# Button.net
KiCad netlist of a schematic drawn in Altium Designer
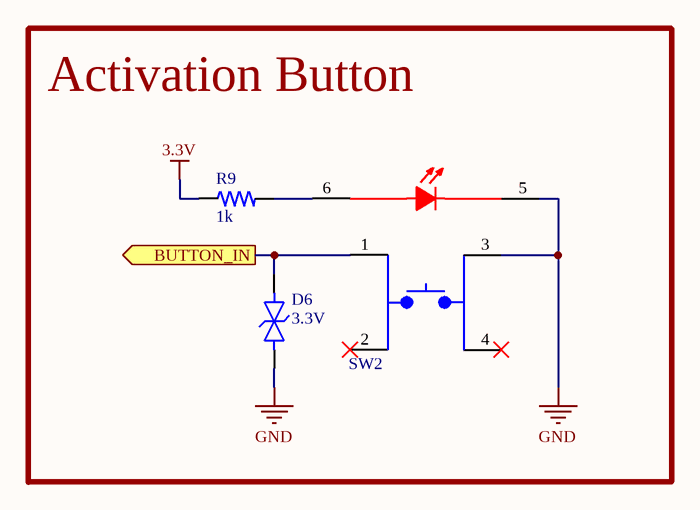
[diagram p0: Button.SchDoc]

(export (version "E")
  (design (tool "Eeschema 10.0.6"))
  (components
    (comp (ref "D6")
      (value "DESD3V3E1BL-7B")
      (footprint "Christmas-2024_TSO-PCB:0402-TVS")
      (description "TVS DIODE 3.3VWM 7VC DFN1006-2")
      (fields (field (name "MFR") "Diodes Incorporated") (field (name "VRS") "3.3V"))
      (libsource (lib "Christmas-2024_TSO-PCB") (part "TVS Diode 3.3V Bi"))
    )
    (comp (ref "R9")
      (value "1k")
      (footprint "Christmas-2024_TSO-PCB:0402R")
      (description "Resistor")
      (fields (field (name "MFR") "YAGEO") (field (name "Comment") "RES"))
      (libsource (lib "Christmas-2024_TSO-PCB") (part "RES"))
    )
    (comp (ref "SW2")
      (value "SPDT PUSH BUTTON SWITCH")
      (footprint "Christmas-2024_TSO-PCB:TL1265RQSCLR")
      (description "SWITCH TACTILE SPST-NO 0.05A 12V, Red Illumination")
      (fields (field (name "MFR") "E-Switch"))
      (libsource (lib "Christmas-2024_TSO-PCB") (part "SPDT PUSH BUTTON SWITCH"))
    )
  )
  (nets
    (net (code "1") (name "/BUTTON_IN") (class "Default")
      (node (ref "D6") (pin "1") (pinfunction "1_1") (pintype "passive"))
      (node (ref "SW2") (pin "1") (pinfunction "1_1") (pintype "passive"))
    )
    (net (code "2") (name "3.3V") (class "Default")
      (node (ref "R9") (pin "1") (pinfunction "1_1") (pintype "passive"))
    )
    (net (code "3") (name "GND") (class "Default")
      (node (ref "D6") (pin "2") (pinfunction "2_2") (pintype "passive"))
      (node (ref "SW2") (pin "3") (pinfunction "3_3") (pintype "passive"))
      (node (ref "SW2") (pin "5") (pinfunction "5_5") (pintype "passive"))
    )
    (net (code "4") (name "Net-(R9-Pad2)") (class "Default")
      (node (ref "R9") (pin "2") (pinfunction "2_2") (pintype "passive"))
      (node (ref "SW2") (pin "6") (pinfunction "6_6") (pintype "passive"))
    )
    (net (code "5") (name "unconnected-(SW2-Pad2)") (class "Default")
      (node (ref "SW2") (pin "2") (pinfunction "2_2") (pintype "passive+no_connect"))
    )
    (net (code "6") (name "unconnected-(SW2-Pad4)") (class "Default")
      (node (ref "SW2") (pin "4") (pinfunction "4_4") (pintype "passive+no_connect"))
    )
  )
)
